# interface.net
KiCad netlist of a schematic drawn in EAGLE
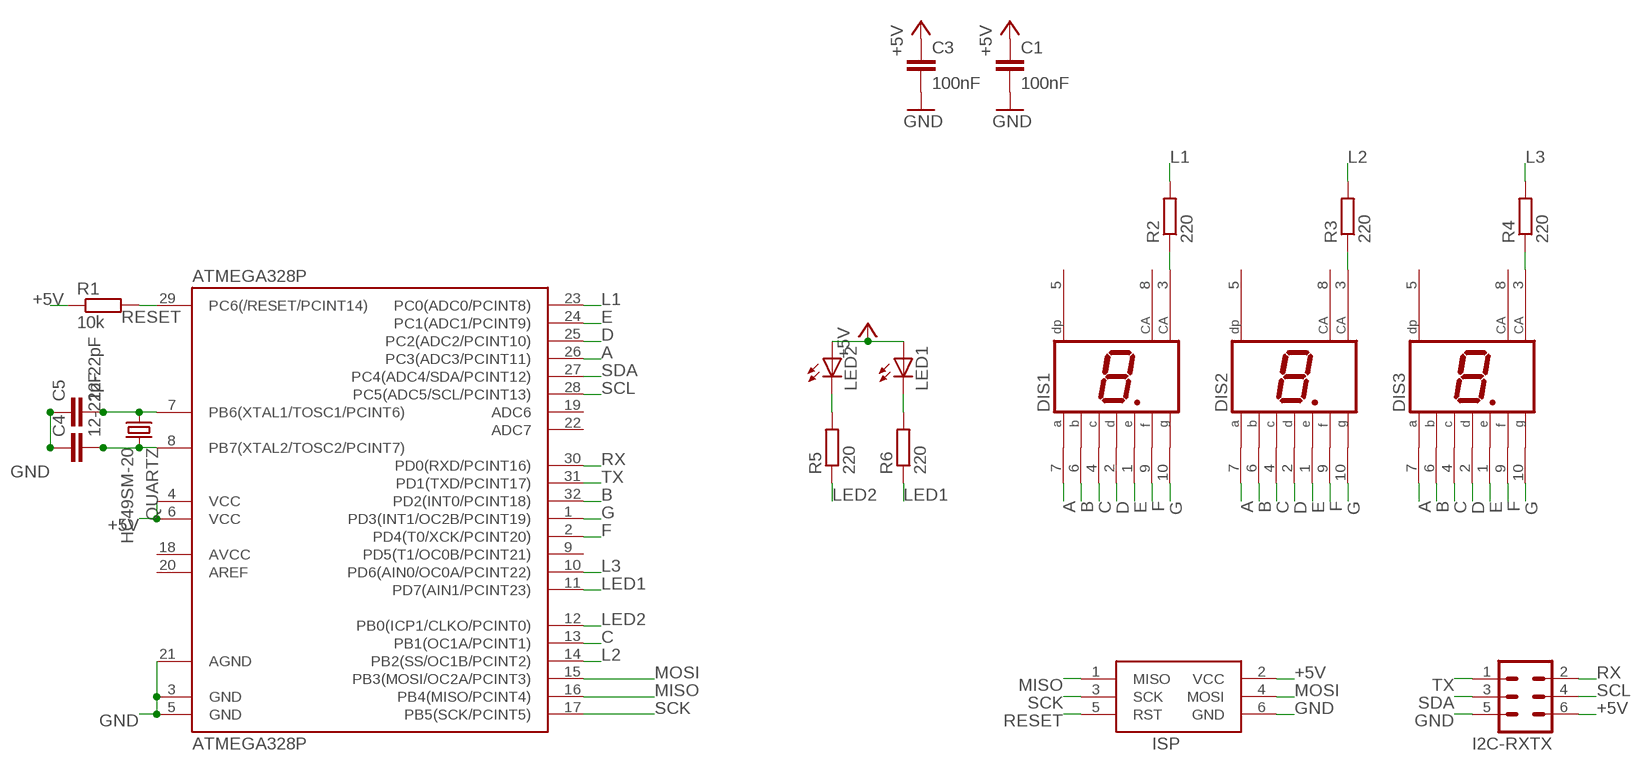
[diagram p0: schematic, sheet 1]

(export (version "E")
  (design (tool "Eeschema 10.0.6"))
  (components
    (comp (ref "ATMEGA328P")
      (value "ATMEGA328P")
      (footprint "eagle-import:TQFP32-08")
      (libsource (lib "eagle-import") (part "MEGA48/88/168-AU"))
    )
    (comp (ref "C1")
      (value "100nF")
      (footprint "eagle-import:C0805")
      (libsource (lib "eagle-import") (part "C-EUC0805"))
    )
    (comp (ref "C3")
      (value "100nF")
      (footprint "eagle-import:C0805")
      (libsource (lib "eagle-import") (part "C-EUC0805"))
    )
    (comp (ref "C4")
      (value "12-22pF")
      (footprint "eagle-import:C0805")
      (libsource (lib "eagle-import") (part "C-EUC0805"))
    )
    (comp (ref "C5")
      (value "12-22pF")
      (footprint "eagle-import:C0805")
      (libsource (lib "eagle-import") (part "C-EUC0805"))
    )
    (comp (ref "DIS1")
      (value "HD-H101")
      (footprint "eagle-import:HDSP-M")
      (libsource (lib "eagle-import") (part "HD-H101"))
    )
    (comp (ref "DIS2")
      (value "HD-H101")
      (footprint "eagle-import:HDSP-M")
      (libsource (lib "eagle-import") (part "HD-H101"))
    )
    (comp (ref "DIS3")
      (value "HD-H101")
      (footprint "eagle-import:HDSP-M")
      (libsource (lib "eagle-import") (part "HD-H101"))
    )
    (comp (ref "I2C-RXTX")
      (value "MA03-2")
      (footprint "eagle-import:MA03-2")
      (libsource (lib "eagle-import") (part "MA03-2"))
    )
    (comp (ref "ISP")
      (value "AVRISP-6")
      (footprint "eagle-import:AVRISP")
      (libsource (lib "eagle-import") (part "AVRISP-6"))
    )
    (comp (ref "LED1")
      (value "LED5MM")
      (footprint "eagle-import:LED5MM")
      (libsource (lib "eagle-import") (part "LED5MM"))
    )
    (comp (ref "LED2")
      (value "LED5MM")
      (footprint "eagle-import:LED5MM")
      (libsource (lib "eagle-import") (part "LED5MM"))
    )
    (comp (ref "QUARTZ")
      (value "HC49SM-20")
      (footprint "eagle-import:HC49UP")
      (libsource (lib "eagle-import") (part "CRYSTALHC49UP"))
    )
    (comp (ref "R1")
      (value "10k")
      (footprint "eagle-import:R0805")
      (libsource (lib "eagle-import") (part "R-EU_R0805"))
    )
    (comp (ref "R2")
      (value "220")
      (footprint "eagle-import:R0805")
      (libsource (lib "eagle-import") (part "R-EU_R0805"))
    )
    (comp (ref "R3")
      (value "220")
      (footprint "eagle-import:R0805")
      (libsource (lib "eagle-import") (part "R-EU_R0805"))
    )
    (comp (ref "R4")
      (value "220")
      (footprint "eagle-import:R0805")
      (libsource (lib "eagle-import") (part "R-EU_R0805"))
    )
    (comp (ref "R5")
      (value "220")
      (footprint "eagle-import:R0805")
      (libsource (lib "eagle-import") (part "R-EU_R0805"))
    )
    (comp (ref "R6")
      (value "220")
      (footprint "eagle-import:R0805")
      (libsource (lib "eagle-import") (part "R-EU_R0805"))
    )
  )
  (nets
    (net (code "1") (name "+5V") (class "Default")
      (node (ref "ATMEGA328P") (pin "4") (pinfunction "VCC_4") (pintype "power_in"))
      (node (ref "ATMEGA328P") (pin "6") (pinfunction "VCC_6") (pintype "power_in"))
      (node (ref "C1") (pin "1") (pinfunction "1_1") (pintype "passive"))
      (node (ref "C3") (pin "1") (pinfunction "1_1") (pintype "passive"))
      (node (ref "I2C-RXTX") (pin "6") (pinfunction "6_6") (pintype "passive"))
      (node (ref "ISP") (pin "2") (pinfunction "VCC_2") (pintype "power_in"))
      (node (ref "LED1") (pin "A") (pinfunction "A_A") (pintype "passive"))
      (node (ref "LED2") (pin "A") (pinfunction "A_A") (pintype "passive"))
      (node (ref "R1") (pin "1") (pinfunction "1_1") (pintype "passive"))
    )
    (net (code "2") (name "/A") (class "Default")
      (node (ref "ATMEGA328P") (pin "26") (pinfunction "PC3(ADC3/PCINT11)_26") (pintype "bidirectional"))
      (node (ref "DIS1") (pin "7") (pinfunction "A_7") (pintype "passive"))
      (node (ref "DIS2") (pin "7") (pinfunction "A_7") (pintype "passive"))
      (node (ref "DIS3") (pin "7") (pinfunction "A_7") (pintype "passive"))
    )
    (net (code "3") (name "/B") (class "Default")
      (node (ref "ATMEGA328P") (pin "32") (pinfunction "PD2(INT0/PCINT18)_32") (pintype "bidirectional"))
      (node (ref "DIS1") (pin "6") (pinfunction "B_6") (pintype "passive"))
      (node (ref "DIS2") (pin "6") (pinfunction "B_6") (pintype "passive"))
      (node (ref "DIS3") (pin "6") (pinfunction "B_6") (pintype "passive"))
    )
    (net (code "4") (name "/C") (class "Default")
      (node (ref "ATMEGA328P") (pin "13") (pinfunction "PB1(OC1A/PCINT1)_13") (pintype "bidirectional"))
      (node (ref "DIS1") (pin "4") (pinfunction "C_4") (pintype "passive"))
      (node (ref "DIS2") (pin "4") (pinfunction "C_4") (pintype "passive"))
      (node (ref "DIS3") (pin "4") (pinfunction "C_4") (pintype "passive"))
    )
    (net (code "5") (name "/D") (class "Default")
      (node (ref "ATMEGA328P") (pin "25") (pinfunction "PC2(ADC2/PCINT10)_25") (pintype "bidirectional"))
      (node (ref "DIS1") (pin "2") (pinfunction "D_2") (pintype "passive"))
      (node (ref "DIS2") (pin "2") (pinfunction "D_2") (pintype "passive"))
      (node (ref "DIS3") (pin "2") (pinfunction "D_2") (pintype "passive"))
    )
    (net (code "6") (name "/E") (class "Default")
      (node (ref "ATMEGA328P") (pin "24") (pinfunction "PC1(ADC1/PCINT9)_24") (pintype "bidirectional"))
      (node (ref "DIS1") (pin "1") (pinfunction "E_1") (pintype "passive"))
      (node (ref "DIS2") (pin "1") (pinfunction "E_1") (pintype "passive"))
      (node (ref "DIS3") (pin "1") (pinfunction "E_1") (pintype "passive"))
    )
    (net (code "7") (name "/F") (class "Default")
      (node (ref "ATMEGA328P") (pin "2") (pinfunction "PD4(T0/XCK/PCINT20)_2") (pintype "bidirectional"))
      (node (ref "DIS1") (pin "9") (pinfunction "F_9") (pintype "passive"))
      (node (ref "DIS2") (pin "9") (pinfunction "F_9") (pintype "passive"))
      (node (ref "DIS3") (pin "9") (pinfunction "F_9") (pintype "passive"))
    )
    (net (code "8") (name "/G") (class "Default")
      (node (ref "ATMEGA328P") (pin "1") (pinfunction "PD3(INT1/OC2B/PCINT19)_1") (pintype "bidirectional"))
      (node (ref "DIS1") (pin "10") (pinfunction "G_10") (pintype "passive"))
      (node (ref "DIS2") (pin "10") (pinfunction "G_10") (pintype "passive"))
      (node (ref "DIS3") (pin "10") (pinfunction "G_10") (pintype "passive"))
    )
    (net (code "9") (name "/L1") (class "Default")
      (node (ref "ATMEGA328P") (pin "23") (pinfunction "PC0(ADC0/PCINT8)_23") (pintype "bidirectional"))
      (node (ref "R2") (pin "2") (pinfunction "2_2") (pintype "passive"))
    )
    (net (code "10") (name "/L2") (class "Default")
      (node (ref "ATMEGA328P") (pin "14") (pinfunction "PB2(SS/OC1B/PCINT2)_14") (pintype "bidirectional"))
      (node (ref "R3") (pin "2") (pinfunction "2_2") (pintype "passive"))
    )
    (net (code "11") (name "/L3") (class "Default")
      (node (ref "ATMEGA328P") (pin "10") (pinfunction "PD6(AIN0/OC0A/PCINT22)_10") (pintype "bidirectional"))
      (node (ref "R4") (pin "2") (pinfunction "2_2") (pintype "passive"))
    )
    (net (code "12") (name "/LED1") (class "Default")
      (node (ref "ATMEGA328P") (pin "11") (pinfunction "PD7(AIN1/PCINT23)_11") (pintype "bidirectional"))
      (node (ref "R6") (pin "1") (pinfunction "1_1") (pintype "passive"))
    )
    (net (code "13") (name "/LED2") (class "Default")
      (node (ref "ATMEGA328P") (pin "12") (pinfunction "PB0(ICP1/CLKO/PCINT0)_12") (pintype "bidirectional"))
      (node (ref "R5") (pin "1") (pinfunction "1_1") (pintype "passive"))
    )
    (net (code "14") (name "/MISO") (class "Default")
      (node (ref "ATMEGA328P") (pin "16") (pinfunction "PB4(MISO/PCINT4)_16") (pintype "bidirectional"))
      (node (ref "ISP") (pin "1") (pinfunction "MISO_1") (pintype "input"))
    )
    (net (code "15") (name "/MOSI") (class "Default")
      (node (ref "ATMEGA328P") (pin "15") (pinfunction "PB3(MOSI/OC2A/PCINT3)_15") (pintype "bidirectional"))
      (node (ref "ISP") (pin "4") (pinfunction "MOSI_4") (pintype "output"))
    )
    (net (code "16") (name "/RESET") (class "Default")
      (node (ref "ATMEGA328P") (pin "29") (pinfunction "PC6(/RESET/PCINT14)_29") (pintype "bidirectional"))
      (node (ref "ISP") (pin "5") (pinfunction "RST_5") (pintype "output"))
      (node (ref "R1") (pin "2") (pinfunction "2_2") (pintype "passive"))
    )
    (net (code "17") (name "/RX") (class "Default")
      (node (ref "ATMEGA328P") (pin "30") (pinfunction "PD0(RXD/PCINT16)_30") (pintype "bidirectional"))
      (node (ref "I2C-RXTX") (pin "2") (pinfunction "2_2") (pintype "passive"))
    )
    (net (code "18") (name "/SCK") (class "Default")
      (node (ref "ATMEGA328P") (pin "17") (pinfunction "PB5(SCK/PCINT5)_17") (pintype "bidirectional"))
      (node (ref "ISP") (pin "3") (pinfunction "SCK_3") (pintype "output"))
    )
    (net (code "19") (name "/SCL") (class "Default")
      (node (ref "ATMEGA328P") (pin "28") (pinfunction "PC5(ADC5/SCL/PCINT13)_28") (pintype "bidirectional"))
      (node (ref "I2C-RXTX") (pin "4") (pinfunction "4_4") (pintype "passive"))
    )
    (net (code "20") (name "/SDA") (class "Default")
      (node (ref "ATMEGA328P") (pin "27") (pinfunction "PC4(ADC4/SDA/PCINT12)_27") (pintype "bidirectional"))
      (node (ref "I2C-RXTX") (pin "3") (pinfunction "3_3") (pintype "passive"))
    )
    (net (code "21") (name "/TX") (class "Default")
      (node (ref "ATMEGA328P") (pin "31") (pinfunction "PD1(TXD/PCINT17)_31") (pintype "bidirectional"))
      (node (ref "I2C-RXTX") (pin "1") (pinfunction "1_1") (pintype "passive"))
    )
    (net (code "22") (name "GND") (class "Default")
      (node (ref "ATMEGA328P") (pin "21") (pinfunction "AGND_21") (pintype "power_in"))
      (node (ref "ATMEGA328P") (pin "3") (pinfunction "GND_3") (pintype "power_in"))
      (node (ref "ATMEGA328P") (pin "5") (pinfunction "GND_5") (pintype "power_in"))
      (node (ref "C1") (pin "2") (pinfunction "2_2") (pintype "passive"))
      (node (ref "C3") (pin "2") (pinfunction "2_2") (pintype "passive"))
      (node (ref "C4") (pin "1") (pinfunction "1_1") (pintype "passive"))
      (node (ref "C5") (pin "1") (pinfunction "1_1") (pintype "passive"))
      (node (ref "I2C-RXTX") (pin "5") (pinfunction "5_5") (pintype "passive"))
      (node (ref "ISP") (pin "6") (pinfunction "GND_6") (pintype "power_in"))
    )
    (net (code "23") (name "Net-(ATMEGA328P-PB6(XTAL1{slash}TOSC1{slash}PCINT6))") (class "Default")
      (node (ref "ATMEGA328P") (pin "7") (pinfunction "PB6(XTAL1/TOSC1/PCINT6)_7") (pintype "bidirectional"))
      (node (ref "C5") (pin "2") (pinfunction "2_2") (pintype "passive"))
      (node (ref "QUARTZ") (pin "1") (pinfunction "1_1") (pintype "passive"))
    )
    (net (code "24") (name "Net-(ATMEGA328P-PB7(XTAL2{slash}TOSC2{slash}PCINT7))") (class "Default")
      (node (ref "ATMEGA328P") (pin "8") (pinfunction "PB7(XTAL2/TOSC2/PCINT7)_8") (pintype "bidirectional"))
      (node (ref "C4") (pin "2") (pinfunction "2_2") (pintype "passive"))
      (node (ref "QUARTZ") (pin "2") (pinfunction "2_2") (pintype "passive"))
    )
    (net (code "25") (name "Net-(DIS1-CA-Pad3)") (class "Default")
      (node (ref "DIS1") (pin "3") (pinfunction "CA_3") (pintype "passive"))
      (node (ref "R2") (pin "1") (pinfunction "1_1") (pintype "passive"))
    )
    (net (code "26") (name "Net-(DIS2-CA-Pad3)") (class "Default")
      (node (ref "DIS2") (pin "3") (pinfunction "CA_3") (pintype "passive"))
      (node (ref "R3") (pin "1") (pinfunction "1_1") (pintype "passive"))
    )
    (net (code "27") (name "Net-(DIS3-CA-Pad3)") (class "Default")
      (node (ref "DIS3") (pin "3") (pinfunction "CA_3") (pintype "passive"))
      (node (ref "R4") (pin "1") (pinfunction "1_1") (pintype "passive"))
    )
    (net (code "28") (name "Net-(LED1-C)") (class "Default")
      (node (ref "LED1") (pin "K") (pinfunction "C_K") (pintype "passive"))
      (node (ref "R6") (pin "2") (pinfunction "2_2") (pintype "passive"))
    )
    (net (code "29") (name "Net-(LED2-C)") (class "Default")
      (node (ref "LED2") (pin "K") (pinfunction "C_K") (pintype "passive"))
      (node (ref "R5") (pin "2") (pinfunction "2_2") (pintype "passive"))
    )
    (net (code "30") (name "unconnected-(ATMEGA328P-ADC6-Pad19)") (class "Default")
      (node (ref "ATMEGA328P") (pin "19") (pinfunction "ADC6_19") (pintype "passive"))
    )
    (net (code "31") (name "unconnected-(ATMEGA328P-ADC7-Pad22)") (class "Default")
      (node (ref "ATMEGA328P") (pin "22") (pinfunction "ADC7_22") (pintype "passive"))
    )
    (net (code "32") (name "unconnected-(ATMEGA328P-AREF-Pad20)") (class "Default")
      (node (ref "ATMEGA328P") (pin "20") (pinfunction "AREF_20") (pintype "passive"))
    )
    (net (code "33") (name "unconnected-(ATMEGA328P-AVCC-Pad18)") (class "Default")
      (node (ref "ATMEGA328P") (pin "18") (pinfunction "AVCC_18") (pintype "passive"))
    )
    (net (code "34") (name "unconnected-(ATMEGA328P-PD5(T1{slash}OC0B{slash}PCINT21)-Pad9)") (class "Default")
      (node (ref "ATMEGA328P") (pin "9") (pinfunction "PD5(T1/OC0B/PCINT21)_9") (pintype "bidirectional"))
    )
    (net (code "35") (name "unconnected-(DIS1-CA-Pad8)") (class "Default")
      (node (ref "DIS1") (pin "8") (pinfunction "CA_8") (pintype "passive"))
    )
    (net (code "36") (name "unconnected-(DIS1-DP-Pad5)") (class "Default")
      (node (ref "DIS1") (pin "5") (pinfunction "DP_5") (pintype "passive"))
    )
    (net (code "37") (name "unconnected-(DIS2-CA-Pad8)") (class "Default")
      (node (ref "DIS2") (pin "8") (pinfunction "CA_8") (pintype "passive"))
    )
    (net (code "38") (name "unconnected-(DIS2-DP-Pad5)") (class "Default")
      (node (ref "DIS2") (pin "5") (pinfunction "DP_5") (pintype "passive"))
    )
    (net (code "39") (name "unconnected-(DIS3-CA-Pad8)") (class "Default")
      (node (ref "DIS3") (pin "8") (pinfunction "CA_8") (pintype "passive"))
    )
    (net (code "40") (name "unconnected-(DIS3-DP-Pad5)") (class "Default")
      (node (ref "DIS3") (pin "5") (pinfunction "DP_5") (pintype "passive"))
    )
  )
)
